# Simple_LNA.net
KiCad netlist of a schematic drawn in EAGLE
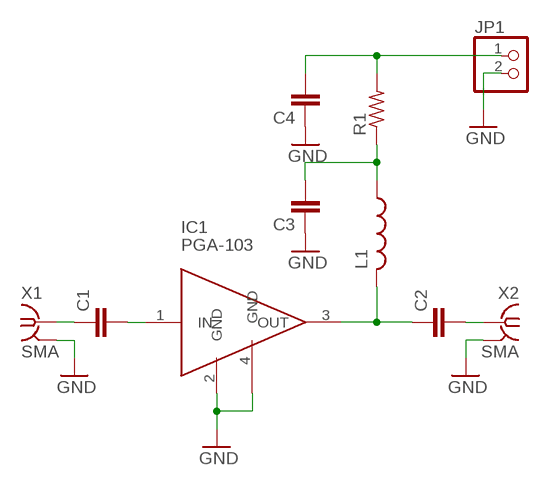
[diagram p0: schematic, sheet 1]

(export (version "E")
  (design (tool "Eeschema 10.0.6"))
  (components
    (comp (ref "C1")
      (value "C-EUC0805")
      (footprint "eagle-import:C0805")
      (libsource (lib "eagle-import") (part "C-EUC0805"))
    )
    (comp (ref "C2")
      (value "C-EUC0805")
      (footprint "eagle-import:C0805")
      (libsource (lib "eagle-import") (part "C-EUC0805"))
    )
    (comp (ref "C3")
      (value "C-EUC0805")
      (footprint "eagle-import:C0805")
      (libsource (lib "eagle-import") (part "C-EUC0805"))
    )
    (comp (ref "C4")
      (value "C-EUC0805")
      (footprint "eagle-import:C0805")
      (libsource (lib "eagle-import") (part "C-EUC0805"))
    )
    (comp (ref "IC1")
      (value "PGA-103")
      (footprint "eagle-import:SOT89")
      (libsource (lib "eagle-import") (part "PGA-103"))
    )
    (comp (ref "JP1")
      (value "PINHD-1X2")
      (footprint "eagle-import:1X02")
      (libsource (lib "eagle-import") (part "PINHD-1X2"))
    )
    (comp (ref "L1")
      (value "L-USL3216C")
      (footprint "eagle-import:L3216C")
      (libsource (lib "eagle-import") (part "L-USL3216C"))
    )
    (comp (ref "R1")
      (value "R-US_R0805")
      (footprint "eagle-import:R0805")
      (libsource (lib "eagle-import") (part "R-US_R0805"))
    )
    (comp (ref "X1")
      (value "SMA")
      (footprint "eagle-import:J502-ND-142-0701-801_806")
      (fields (field (name "MF") "JOHNSON COMPONENTS") (field (name "MPN") "142-0701-801"))
      (libsource (lib "eagle-import") (part "SMA-142-0701-801/806"))
    )
    (comp (ref "X2")
      (value "SMA")
      (footprint "eagle-import:J502-ND-142-0701-801_806")
      (fields (field (name "MF") "JOHNSON COMPONENTS") (field (name "MPN") "142-0701-801"))
      (libsource (lib "eagle-import") (part "SMA-142-0701-801/806"))
    )
  )
  (nets
    (net (code "1") (name "GND") (class "Default")
      (node (ref "C3") (pin "1") (pinfunction "1_1") (pintype "passive"))
      (node (ref "C4") (pin "1") (pinfunction "1_1") (pintype "passive"))
      (node (ref "IC1") (pin "2") (pinfunction "GND_2") (pintype "power_in"))
      (node (ref "IC1") (pin "4") (pinfunction "GND_4") (pintype "power_in"))
      (node (ref "JP1") (pin "2") (pinfunction "2_2") (pintype "passive"))
      (node (ref "X1") (pin "G@1") (pinfunction "2_G@1") (pintype "passive"))
      (node (ref "X1") (pin "G@2") (pinfunction "2_G@2") (pintype "passive"))
      (node (ref "X1") (pin "G@3") (pinfunction "2_G@3") (pintype "passive"))
      (node (ref "X1") (pin "G@4") (pinfunction "2_G@4") (pintype "passive"))
      (node (ref "X2") (pin "G@1") (pinfunction "2_G@1") (pintype "passive"))
      (node (ref "X2") (pin "G@2") (pinfunction "2_G@2") (pintype "passive"))
      (node (ref "X2") (pin "G@3") (pinfunction "2_G@3") (pintype "passive"))
      (node (ref "X2") (pin "G@4") (pinfunction "2_G@4") (pintype "passive"))
    )
    (net (code "2") (name "Net-(C1-Pad1)") (class "Default")
      (node (ref "C1") (pin "1") (pinfunction "1_1") (pintype "passive"))
      (node (ref "X1") (pin "1") (pinfunction "1_1") (pintype "passive"))
    )
    (net (code "3") (name "Net-(C2-Pad2)") (class "Default")
      (node (ref "C2") (pin "2") (pinfunction "2_2") (pintype "passive"))
      (node (ref "X2") (pin "1") (pinfunction "1_1") (pintype "passive"))
    )
    (net (code "4") (name "Net-(C3-Pad2)") (class "Default")
      (node (ref "C3") (pin "2") (pinfunction "2_2") (pintype "passive"))
      (node (ref "L1") (pin "1") (pinfunction "1_1") (pintype "passive"))
      (node (ref "R1") (pin "1") (pinfunction "1_1") (pintype "passive"))
    )
    (net (code "5") (name "Net-(C4-Pad2)") (class "Default")
      (node (ref "C4") (pin "2") (pinfunction "2_2") (pintype "passive"))
      (node (ref "JP1") (pin "1") (pinfunction "1_1") (pintype "passive"))
      (node (ref "R1") (pin "2") (pinfunction "2_2") (pintype "passive"))
    )
    (net (code "6") (name "Net-(IC1-IN)") (class "Default")
      (node (ref "C1") (pin "2") (pinfunction "2_2") (pintype "passive"))
      (node (ref "IC1") (pin "1") (pinfunction "IN_1") (pintype "input"))
    )
    (net (code "7") (name "Net-(IC1-OUT)") (class "Default")
      (node (ref "C2") (pin "1") (pinfunction "1_1") (pintype "passive"))
      (node (ref "IC1") (pin "3") (pinfunction "OUT_3") (pintype "output"))
      (node (ref "L1") (pin "2") (pinfunction "2_2") (pintype "passive"))
    )
  )
)
